# main.net
KiCad netlist of a schematic drawn in EAGLE
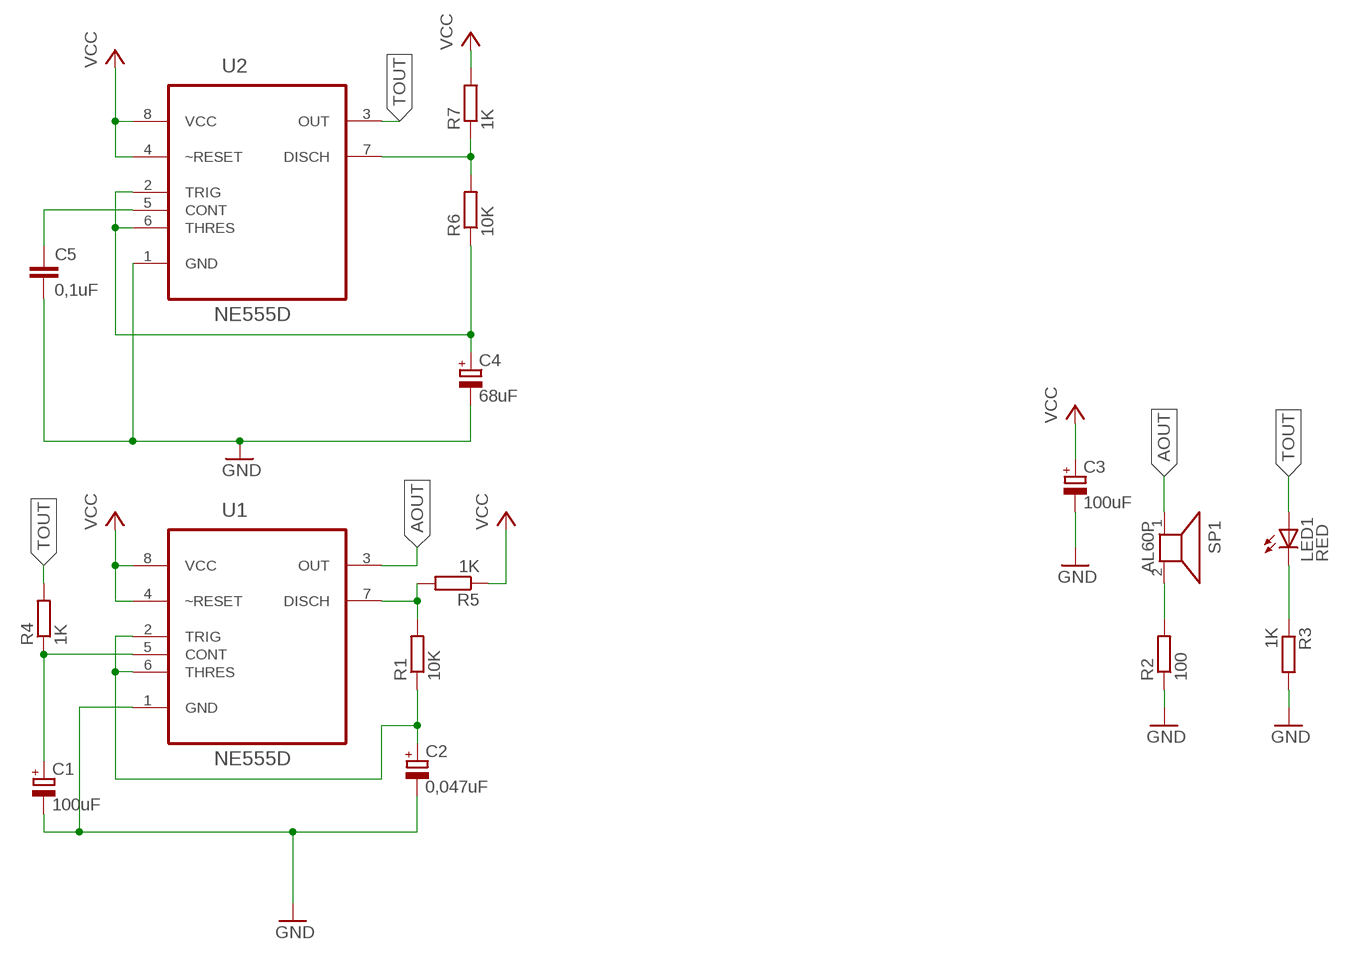
[diagram p0: schematic, sheet 1]

(export (version "E")
  (design (tool "Eeschema 10.0.6"))
  (components
    (comp (ref "C1")
      (value "100uF")
      (footprint "eagle-import:E3,5-8")
      (libsource (lib "eagle-import") (part "CPOL-EUE3.5-8"))
    )
    (comp (ref "C2")
      (value "0,047uF")
      (footprint "eagle-import:E3,5-8")
      (libsource (lib "eagle-import") (part "CPOL-EUE3.5-8"))
    )
    (comp (ref "C3")
      (value "100uF")
      (footprint "eagle-import:E3,5-8")
      (libsource (lib "eagle-import") (part "CPOL-EUE3.5-8"))
    )
    (comp (ref "C4")
      (value "68uF")
      (footprint "eagle-import:E3,5-8")
      (libsource (lib "eagle-import") (part "CPOL-EUE3.5-8"))
    )
    (comp (ref "C5")
      (value "0,1uF")
      (footprint "eagle-import:C025-025X050")
      (libsource (lib "eagle-import") (part "C-EU025-025X050"))
    )
    (comp (ref "LED1")
      (value "RED")
      (footprint "eagle-import:LED5MM")
      (libsource (lib "eagle-import") (part "LED5MM"))
    )
    (comp (ref "R1")
      (value "10K")
      (footprint "eagle-import:0204_7")
      (libsource (lib "eagle-import") (part "R-EU_0204/7"))
    )
    (comp (ref "R2")
      (value "100")
      (footprint "eagle-import:0204_7")
      (libsource (lib "eagle-import") (part "R-EU_0204/7"))
    )
    (comp (ref "R3")
      (value "1K")
      (footprint "eagle-import:0204_7")
      (libsource (lib "eagle-import") (part "R-EU_0204/7"))
    )
    (comp (ref "R4")
      (value "1K")
      (footprint "eagle-import:0204_7")
      (libsource (lib "eagle-import") (part "R-EU_0204/7"))
    )
    (comp (ref "R5")
      (value "1K")
      (footprint "eagle-import:0204_7")
      (libsource (lib "eagle-import") (part "R-EU_0204/7"))
    )
    (comp (ref "R6")
      (value "10K")
      (footprint "eagle-import:0204_7")
      (libsource (lib "eagle-import") (part "R-EU_0204/7"))
    )
    (comp (ref "R7")
      (value "1K")
      (footprint "eagle-import:0204_7")
      (libsource (lib "eagle-import") (part "R-EU_0204/7"))
    )
    (comp (ref "SP1")
      (value "AL60P")
      (footprint "eagle-import:AL60P")
      (libsource (lib "eagle-import") (part "AL60P"))
    )
    (comp (ref "U1")
      (value "NE555D")
      (footprint "eagle-import:SOIC127P600X175-8N")
      (libsource (lib "eagle-import") (part "NE555D"))
    )
    (comp (ref "U2")
      (value "NE555D")
      (footprint "eagle-import:SOIC127P600X175-8N")
      (libsource (lib "eagle-import") (part "NE555D"))
    )
  )
  (nets
    (net (code "1") (name "AOUT") (class "Default")
      (node (ref "SP1") (pin "1") (pinfunction "1_1") (pintype "passive"))
      (node (ref "U1") (pin "3") (pinfunction "OUT_3") (pintype "output"))
    )
    (net (code "2") (name "GND") (class "Default")
      (node (ref "C1") (pin "-") (pinfunction "-_-") (pintype "passive"))
      (node (ref "C2") (pin "-") (pinfunction "-_-") (pintype "passive"))
      (node (ref "C3") (pin "-") (pinfunction "-_-") (pintype "passive"))
      (node (ref "C4") (pin "-") (pinfunction "-_-") (pintype "passive"))
      (node (ref "C5") (pin "2") (pinfunction "2_2") (pintype "passive"))
      (node (ref "R2") (pin "1") (pinfunction "1_1") (pintype "passive"))
      (node (ref "R3") (pin "2") (pinfunction "2_2") (pintype "passive"))
      (node (ref "U1") (pin "1") (pinfunction "GND_1") (pintype "passive"))
      (node (ref "U2") (pin "1") (pinfunction "GND_1") (pintype "passive"))
    )
    (net (code "3") (name "Net-(LED1-C)") (class "Default")
      (node (ref "LED1") (pin "K") (pinfunction "C_K") (pintype "passive"))
      (node (ref "R3") (pin "1") (pinfunction "1_1") (pintype "passive"))
    )
    (net (code "4") (name "Net-(R2-Pad2)") (class "Default")
      (node (ref "R2") (pin "2") (pinfunction "2_2") (pintype "passive"))
      (node (ref "SP1") (pin "2") (pinfunction "2_2") (pintype "passive"))
    )
    (net (code "5") (name "Net-(U1-CONT)") (class "Default")
      (node (ref "C1") (pin "+") (pinfunction "+_+") (pintype "passive"))
      (node (ref "R4") (pin "1") (pinfunction "1_1") (pintype "passive"))
      (node (ref "U1") (pin "5") (pinfunction "CONT_5") (pintype "passive"))
    )
    (net (code "6") (name "Net-(U1-DISCH)") (class "Default")
      (node (ref "R1") (pin "2") (pinfunction "2_2") (pintype "passive"))
      (node (ref "R5") (pin "2") (pinfunction "2_2") (pintype "passive"))
      (node (ref "U1") (pin "7") (pinfunction "DISCH_7") (pintype "passive"))
    )
    (net (code "7") (name "Net-(U1-THRES)") (class "Default")
      (node (ref "C2") (pin "+") (pinfunction "+_+") (pintype "passive"))
      (node (ref "R1") (pin "1") (pinfunction "1_1") (pintype "passive"))
      (node (ref "U1") (pin "2") (pinfunction "TRIG_2") (pintype "input"))
      (node (ref "U1") (pin "6") (pinfunction "THRES_6") (pintype "input"))
    )
    (net (code "8") (name "Net-(U2-CONT)") (class "Default")
      (node (ref "C5") (pin "1") (pinfunction "1_1") (pintype "passive"))
      (node (ref "U2") (pin "5") (pinfunction "CONT_5") (pintype "passive"))
    )
    (net (code "9") (name "Net-(U2-DISCH)") (class "Default")
      (node (ref "R6") (pin "2") (pinfunction "2_2") (pintype "passive"))
      (node (ref "R7") (pin "1") (pinfunction "1_1") (pintype "passive"))
      (node (ref "U2") (pin "7") (pinfunction "DISCH_7") (pintype "passive"))
    )
    (net (code "10") (name "Net-(U2-THRES)") (class "Default")
      (node (ref "C4") (pin "+") (pinfunction "+_+") (pintype "passive"))
      (node (ref "R6") (pin "1") (pinfunction "1_1") (pintype "passive"))
      (node (ref "U2") (pin "2") (pinfunction "TRIG_2") (pintype "input"))
      (node (ref "U2") (pin "6") (pinfunction "THRES_6") (pintype "input"))
    )
    (net (code "11") (name "TOUT") (class "Default")
      (node (ref "LED1") (pin "A") (pinfunction "A_A") (pintype "passive"))
      (node (ref "R4") (pin "2") (pinfunction "2_2") (pintype "passive"))
      (node (ref "U2") (pin "3") (pinfunction "OUT_3") (pintype "output"))
    )
    (net (code "12") (name "VCC") (class "Default")
      (node (ref "C3") (pin "+") (pinfunction "+_+") (pintype "passive"))
      (node (ref "R5") (pin "1") (pinfunction "1_1") (pintype "passive"))
      (node (ref "R7") (pin "2") (pinfunction "2_2") (pintype "passive"))
      (node (ref "U1") (pin "4") (pinfunction "~{RESET}_4") (pintype "input"))
      (node (ref "U1") (pin "8") (pinfunction "VCC_8") (pintype "power_in"))
      (node (ref "U2") (pin "4") (pinfunction "~{RESET}_4") (pintype "input"))
      (node (ref "U2") (pin "8") (pinfunction "VCC_8") (pintype "power_in"))
    )
  )
)
